# Power_Supply.net
KiCad netlist of a schematic drawn in Altium Designer
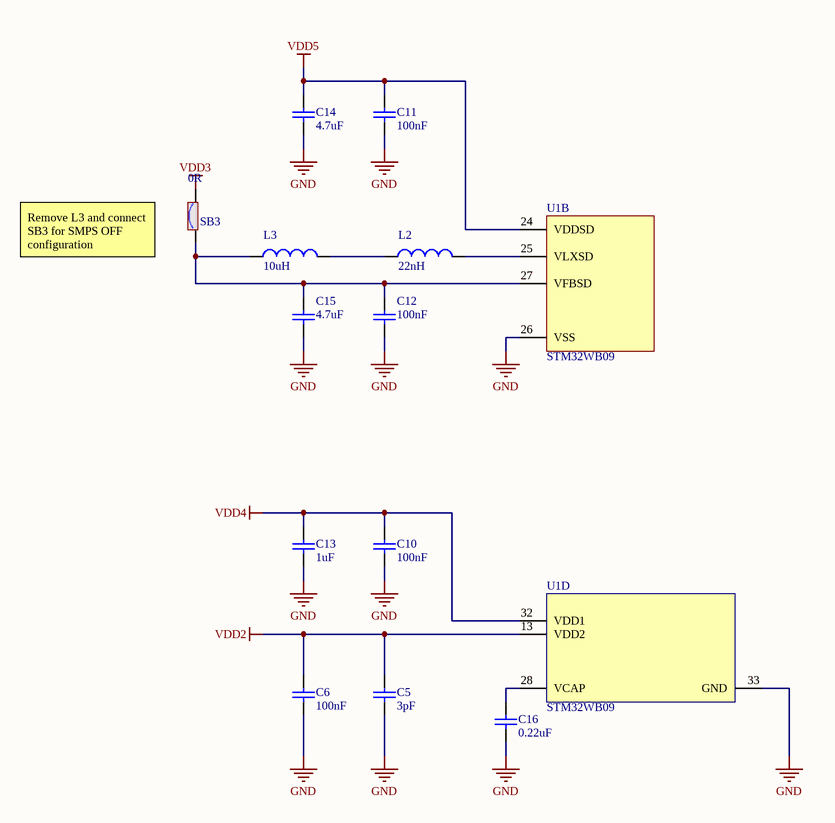
[diagram p0: Power_Supply.SchDoc]

(export (version "E")
  (design (tool "Eeschema 10.0.6"))
  (components
    (comp (ref "C5")
      (value "3pF")
      (footprint "C0402")
      (description "Capacitor, C0G, 3 pF, 50V, NPO, ±0.1pF, 0402, T=0.5mm")
      (fields
        (field (name "INTERNAL_PART_NUMBER") "MCD-03898")
        (field (name "MANUFACTURER") "WALSIN TECHNOLOGY CORPORATION")
      )
      (libsource (lib "MCD_PARTS_database") (part "Capacitor"))
    )
    (comp (ref "C6")
      (value "100nF")
      (footprint "MCD_PARTS:C0402")
      (description "Capacitor, MLCC, 100nF, ±10%, X7R, 25V, 0402, T=0.5mm")
      (fields (field (name "INTERNAL_PART_NUMBER") "MCD-03442") (field (name "MANUFACTURER") "MURATA"))
      (libsource (lib "MCD_PARTS_database") (part "Capacitor"))
    )
    (comp (ref "C10")
      (value "100nF")
      (footprint "MCD_PARTS:C0402")
      (description "Capacitor, MLCC, 100nF, ±10%, X7R, 25V, 0402, T=0.5mm")
      (fields (field (name "INTERNAL_PART_NUMBER") "MCD-03442") (field (name "MANUFACTURER") "MURATA"))
      (libsource (lib "MCD_PARTS_database") (part "Capacitor"))
    )
    (comp (ref "C11")
      (value "100nF")
      (footprint "MCD_PARTS:C0402")
      (description "Capacitor, MLCC, 100nF, ±10%, X7R, 25V, 0402, T=0.5mm")
      (fields (field (name "INTERNAL_PART_NUMBER") "MCD-03442") (field (name "MANUFACTURER") "MURATA"))
      (libsource (lib "MCD_PARTS_database") (part "Capacitor"))
    )
    (comp (ref "C12")
      (value "100nF")
      (footprint "MCD_PARTS:C0402")
      (description "Capacitor, MLCC, 100nF, ±10%, X7R, 25V, 0402, T=0.5mm")
      (fields (field (name "INTERNAL_PART_NUMBER") "MCD-03442") (field (name "MANUFACTURER") "MURATA"))
      (libsource (lib "MCD_PARTS_database") (part "Capacitor"))
    )
    (comp (ref "C13")
      (value "1uF")
      (footprint "MCD_PARTS:C0402")
      (description "Capacitor, MLCC, 1uF, X7R, 6.3V, 0402, ± 10%, T=0.5mm")
      (fields (field (name "INTERNAL_PART_NUMBER") "MCD-03432") (field (name "MANUFACTURER") "MURATA"))
      (libsource (lib "MCD_PARTS_database") (part "Capacitor"))
    )
    (comp (ref "C14")
      (value "4.7uF")
      (footprint "MCD_PARTS:C0402")
      (description "Capacitor, MLCC, 4.7uF, X5R, 10 V, 0402, ± 20%, T=0.5mm")
      (fields (field (name "INTERNAL_PART_NUMBER") "MCD-03431") (field (name "MANUFACTURER") "MURATA"))
      (libsource (lib "MCD_PARTS_database") (part "Capacitor"))
    )
    (comp (ref "C15")
      (value "4.7uF")
      (footprint "MCD_PARTS:C0402")
      (description "Capacitor, MLCC, 4.7uF, X5R, 10 V, 0402, ± 20%, T=0.5mm")
      (fields (field (name "INTERNAL_PART_NUMBER") "MCD-03431") (field (name "MANUFACTURER") "MURATA"))
      (libsource (lib "MCD_PARTS_database") (part "Capacitor"))
    )
    (comp (ref "C16")
      (value "0.22uF")
      (footprint "MCD_PARTS:C0402")
      (description "Capacitor, MLCC, 0.22uF, X5R, 6.3V, +/-10%, 0402, T=0.5mm")
      (fields (field (name "INTERNAL_PART_NUMBER") "MCD-03483") (field (name "MANUFACTURER") "YAGEO"))
      (libsource (lib "MCD_PARTS_database") (part "Capacitor"))
    )
    (comp (ref "L2")
      (value "22nH")
      (footprint "MCD_PARTS:C0402")
      (description "Inductor, MLCC, 22nH, ±2%, 350mA, 0.58R, 0402, T=1.45mm")
      (fields (field (name "INTERNAL_PART_NUMBER") "MCD-03439") (field (name "MANUFACTURER") "MURATA"))
      (libsource (lib "MCD_PARTS_database") (part "Inductor"))
    )
    (comp (ref "L3")
      (value "10uH")
      (footprint "MCD_PARTS:IND_0805_MURATA_LQM21")
      (description "Inductor, MLCC, 10uH, ±20%, 300mA, 845mR, 0805, T=1.45mm")
      (fields (field (name "INTERNAL_PART_NUMBER") "MCD-03438") (field (name "MANUFACTURER") "MURATA"))
      (libsource (lib "MCD_PARTS_database") (part "Inductor"))
    )
    (comp (ref "SB3")
      (value "0R")
      (footprint "MCD_PARTS:SOLDER-BRIDGE_R0402-0R")
      (description "Solder Bridge 0402 ON")
      (fields (field (name "INTERNAL_PART_NUMBER") "MCD-01618") (field (name "MANUFACTURER") "YAGEO"))
      (libsource (lib "MCD_PARTS_database") (part "SB_ON"))
    )
    (comp (ref "U1")
      (value "STM32WB09")
      (footprint "ICC_QFN32-EPAD_5X5_P050")
      (description "Bluetooth® Low Energy wireless SoC")
      (fields
        (field (name "INTERNAL_PART_NUMBER") "MCD-03444")
        (field (name "MANUFACTURER") "STMICROELECTRONICS")
      )
      (libsource (lib "MCD_PARTS_database") (part "STM32WB09"))
    )
  )
  (nets
    (net (code "1") (name "GND") (class "Default")
      (node (ref "C10") (pin "1") (pinfunction "1_1") (pintype "passive"))
      (node (ref "C11") (pin "1") (pinfunction "1_1") (pintype "passive"))
      (node (ref "C12") (pin "1") (pinfunction "1_1") (pintype "passive"))
      (node (ref "C13") (pin "1") (pinfunction "1_1") (pintype "passive"))
      (node (ref "C14") (pin "1") (pinfunction "1_1") (pintype "passive"))
      (node (ref "C15") (pin "1") (pinfunction "1_1") (pintype "passive"))
      (node (ref "C16") (pin "1") (pinfunction "1_1") (pintype "passive"))
      (node (ref "C5") (pin "1") (pinfunction "1_1") (pintype "passive"))
      (node (ref "C6") (pin "1") (pinfunction "1_1") (pintype "passive"))
      (node (ref "U1") (pin "26") (pinfunction "VSS_26") (pintype "passive"))
      (node (ref "U1") (pin "33") (pinfunction "GND_33") (pintype "passive"))
    )
    (net (code "2") (name "Net-(L2-Pad1)") (class "Default")
      (node (ref "L2") (pin "1") (pinfunction "1_1") (pintype "passive"))
      (node (ref "L3") (pin "2") (pinfunction "2_2") (pintype "passive"))
    )
    (net (code "3") (name "Net-(U1B-VFBSD)") (class "Default")
      (node (ref "C12") (pin "2") (pinfunction "2_2") (pintype "passive"))
      (node (ref "C15") (pin "2") (pinfunction "2_2") (pintype "passive"))
      (node (ref "L3") (pin "1") (pinfunction "1_1") (pintype "passive"))
      (node (ref "SB3") (pin "1") (pinfunction "1_1") (pintype "passive"))
      (node (ref "U1") (pin "27") (pinfunction "VFBSD_27") (pintype "passive"))
    )
    (net (code "4") (name "Net-(U1B-VLXSD)") (class "Default")
      (node (ref "L2") (pin "2") (pinfunction "2_2") (pintype "passive"))
      (node (ref "U1") (pin "25") (pinfunction "VLXSD_25") (pintype "passive"))
    )
    (net (code "5") (name "Net-(U1D-VCAP)") (class "Default")
      (node (ref "C16") (pin "2") (pinfunction "2_2") (pintype "passive"))
      (node (ref "U1") (pin "28") (pinfunction "VCAP_28") (pintype "passive"))
    )
    (net (code "6") (name "VDD2") (class "Default")
      (node (ref "C5") (pin "2") (pinfunction "2_2") (pintype "passive"))
      (node (ref "C6") (pin "2") (pinfunction "2_2") (pintype "passive"))
      (node (ref "U1") (pin "13") (pinfunction "VDD2_13") (pintype "passive"))
    )
    (net (code "7") (name "VDD3") (class "Default")
      (node (ref "SB3") (pin "2") (pinfunction "2_2") (pintype "passive"))
    )
    (net (code "8") (name "VDD4") (class "Default")
      (node (ref "C10") (pin "2") (pinfunction "2_2") (pintype "passive"))
      (node (ref "C13") (pin "2") (pinfunction "2_2") (pintype "passive"))
      (node (ref "U1") (pin "32") (pinfunction "VDD1_32") (pintype "passive"))
    )
    (net (code "9") (name "VDD5") (class "Default")
      (node (ref "C11") (pin "2") (pinfunction "2_2") (pintype "passive"))
      (node (ref "C14") (pin "2") (pinfunction "2_2") (pintype "passive"))
      (node (ref "U1") (pin "24") (pinfunction "VDDSD_24") (pintype "passive"))
    )
  )
)
